# Transistor-theremin_2026-03-18_10-14-34.net
KiCad netlist of a schematic drawn in EasyEDA Pro
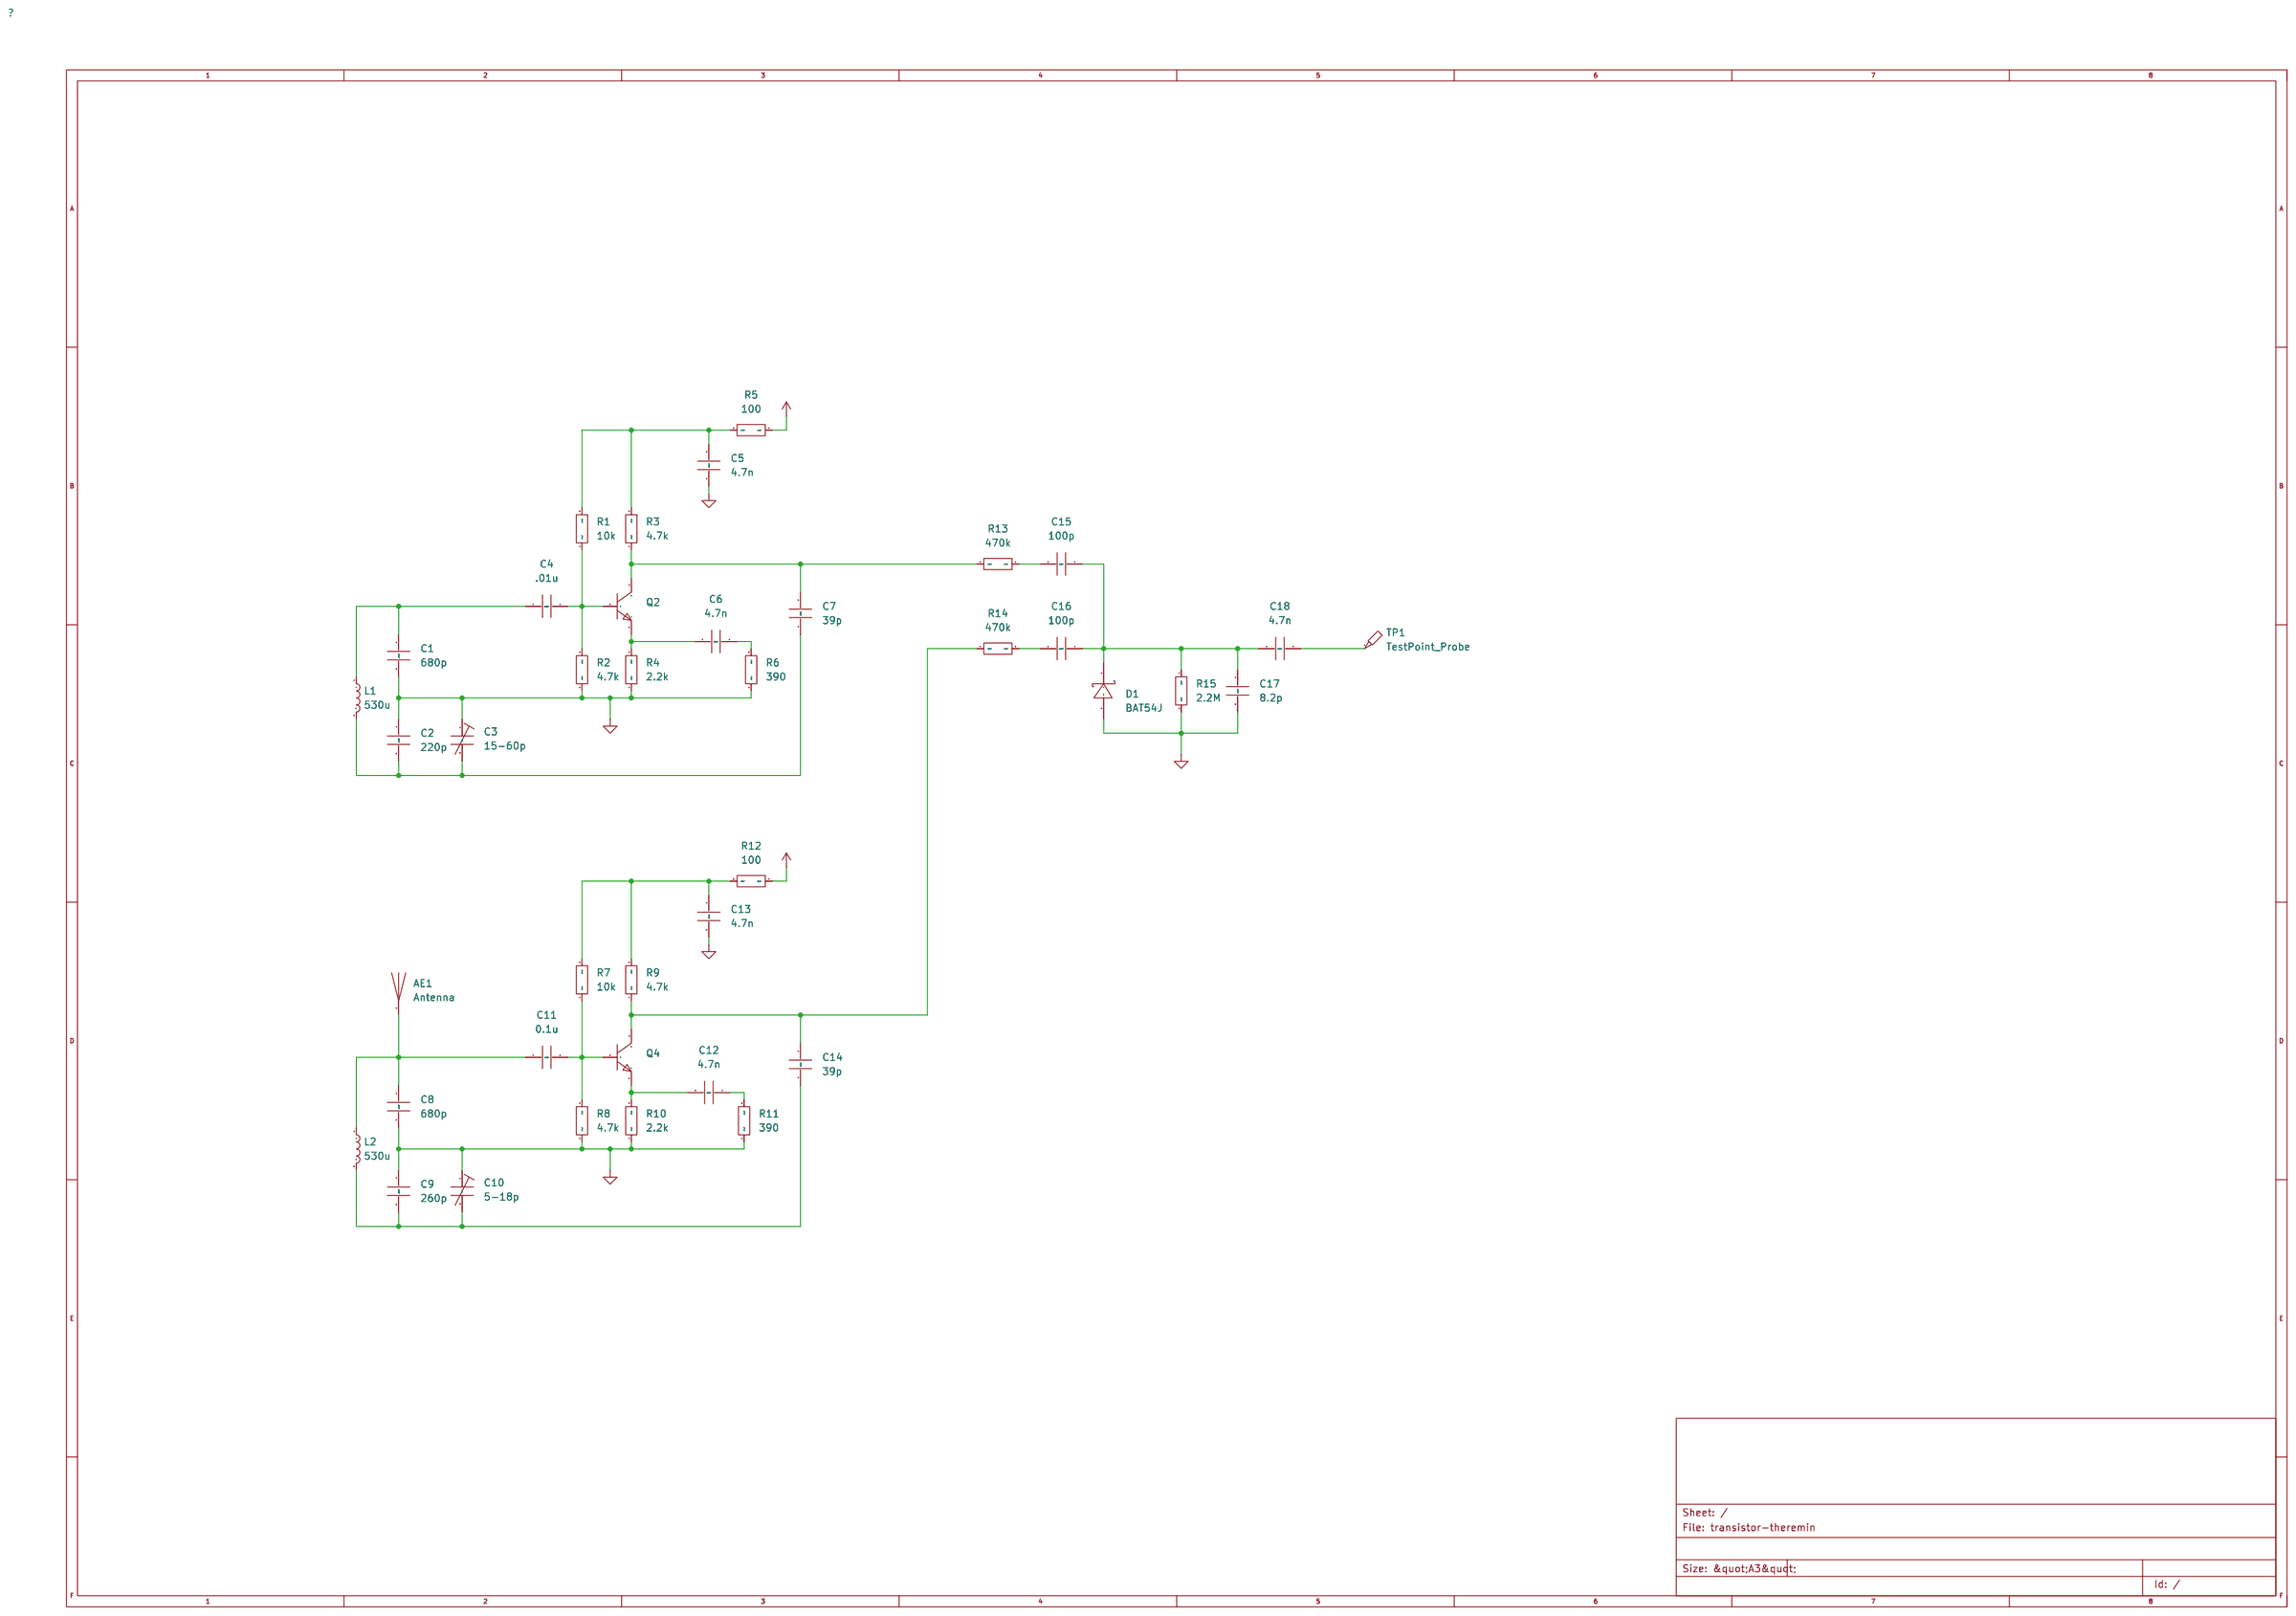
[diagram p0: schematic sheet]

(export (version "E")
  (design (tool "Eeschema 10.0.6"))
  (components
    (comp (ref "AE1") (value "Antenna") (libsource (lib "easyedapro") (part "Device_Antenna")))
    (comp (ref "C1")
      (value "680p")
      (description "Unpolarized capacitor")
      (libsource (lib "easyedapro") (part "Device_C"))
    )
    (comp (ref "C2")
      (value "220p")
      (description "Unpolarized capacitor")
      (libsource (lib "easyedapro") (part "Device_C"))
    )
    (comp (ref "C3")
      (value "15-60p")
      (description "Trimmable capacitor")
      (libsource (lib "easyedapro") (part "Device_C_Trim"))
    )
    (comp (ref "C4")
      (value ".01u")
      (description "Unpolarized capacitor")
      (libsource (lib "easyedapro") (part "Device_C"))
    )
    (comp (ref "C5")
      (value "4.7n")
      (description "Unpolarized capacitor")
      (libsource (lib "easyedapro") (part "Device_C"))
    )
    (comp (ref "C6")
      (value "4.7n")
      (description "Unpolarized capacitor")
      (libsource (lib "easyedapro") (part "Device_C"))
    )
    (comp (ref "C7")
      (value "39p")
      (description "Unpolarized capacitor")
      (libsource (lib "easyedapro") (part "Device_C"))
    )
    (comp (ref "C8")
      (value "680p")
      (description "Unpolarized capacitor")
      (libsource (lib "easyedapro") (part "Device_C"))
    )
    (comp (ref "C9")
      (value "260p")
      (description "Unpolarized capacitor")
      (libsource (lib "easyedapro") (part "Device_C"))
    )
    (comp (ref "C10")
      (value "5-18p")
      (description "Trimmable capacitor")
      (libsource (lib "easyedapro") (part "Device_C_Trim"))
    )
    (comp (ref "C11")
      (value "0.1u")
      (description "Unpolarized capacitor")
      (libsource (lib "easyedapro") (part "Device_C"))
    )
    (comp (ref "C12")
      (value "4.7n")
      (description "Unpolarized capacitor")
      (libsource (lib "easyedapro") (part "Device_C"))
    )
    (comp (ref "C13")
      (value "4.7n")
      (description "Unpolarized capacitor")
      (libsource (lib "easyedapro") (part "Device_C"))
    )
    (comp (ref "C14")
      (value "39p")
      (description "Unpolarized capacitor")
      (libsource (lib "easyedapro") (part "Device_C"))
    )
    (comp (ref "C15")
      (value "100p")
      (description "Unpolarized capacitor")
      (libsource (lib "easyedapro") (part "Device_C"))
    )
    (comp (ref "C16")
      (value "100p")
      (description "Unpolarized capacitor")
      (libsource (lib "easyedapro") (part "Device_C"))
    )
    (comp (ref "C17")
      (value "8.2p")
      (description "Unpolarized capacitor")
      (libsource (lib "easyedapro") (part "Device_C"))
    )
    (comp (ref "C18")
      (value "4.7n")
      (description "Unpolarized capacitor")
      (libsource (lib "easyedapro") (part "Device_C"))
    )
    (comp (ref "D1")
      (value "BAT54J")
      (footprint "easyedapro:SOD-323_L1.8-W1.3-LS2.5-RD")
      (fields (field (name "Manufacturer") "BLUE ROCKET(蓝箭)"))
      (libsource (lib "easyedapro") (part "BAT54J"))
    )
    (comp (ref "L1") (value "530u") (description "Inductor") (libsource (lib "easyedapro") (part "Device_L")))
    (comp (ref "L2") (value "530u") (description "Inductor") (libsource (lib "easyedapro") (part "Device_L")))
    (comp (ref "Q2")
      (value "~")
      (footprint "easyedapro:SOT-23-3_L2.9-W1.3-P1.90-LS2.4-BR")
      (fields (field (name "Manufacturer Part") "MMBT3904") (field (name "Manufacturer") "CJ(江苏长电/长晶)"))
      (libsource (lib "easyedapro") (part "MMBT3904"))
    )
    (comp (ref "Q4")
      (value "~")
      (footprint "easyedapro:SOT-23-3_L2.9-W1.3-P1.90-LS2.4-BR")
      (fields (field (name "Manufacturer Part") "MMBT3904") (field (name "Manufacturer") "CJ(江苏长电/长晶)"))
      (libsource (lib "easyedapro") (part "MMBT3904"))
    )
    (comp (ref "R1") (value "10k") (description "Resistor") (libsource (lib "easyedapro") (part "Device_R")))
    (comp (ref "R2") (value "4.7k") (description "Resistor") (libsource (lib "easyedapro") (part "Device_R")))
    (comp (ref "R3") (value "4.7k") (description "Resistor") (libsource (lib "easyedapro") (part "Device_R")))
    (comp (ref "R4") (value "2.2k") (description "Resistor") (libsource (lib "easyedapro") (part "Device_R")))
    (comp (ref "R5") (value "100") (description "Resistor") (libsource (lib "easyedapro") (part "Device_R")))
    (comp (ref "R6") (value "390") (description "Resistor") (libsource (lib "easyedapro") (part "Device_R")))
    (comp (ref "R7") (value "10k") (description "Resistor") (libsource (lib "easyedapro") (part "Device_R")))
    (comp (ref "R8") (value "4.7k") (description "Resistor") (libsource (lib "easyedapro") (part "Device_R")))
    (comp (ref "R9") (value "4.7k") (description "Resistor") (libsource (lib "easyedapro") (part "Device_R")))
    (comp (ref "R10")
      (value "2.2k")
      (description "Resistor")
      (libsource (lib "easyedapro") (part "Device_R"))
    )
    (comp (ref "R11") (value "390") (description "Resistor") (libsource (lib "easyedapro") (part "Device_R")))
    (comp (ref "R12") (value "100") (description "Resistor") (libsource (lib "easyedapro") (part "Device_R")))
    (comp (ref "R13")
      (value "470k")
      (description "Resistor")
      (libsource (lib "easyedapro") (part "Device_R"))
    )
    (comp (ref "R14")
      (value "470k")
      (description "Resistor")
      (libsource (lib "easyedapro") (part "Device_R"))
    )
    (comp (ref "R15")
      (value "2.2M")
      (description "Resistor")
      (libsource (lib "easyedapro") (part "Device_R"))
    )
    (comp (ref "TP1")
      (value "TestPoint_Probe")
      (description "test point (alternative probe-style design)")
      (libsource (lib "easyedapro") (part "Connector_TestPoint_Probe"))
    )
  )
  (nets
    (net (code "1") (name "Net-(AE1-A)") (class "Default")
      (node (ref "AE1") (pin "1") (pinfunction "A_1") (pintype "input"))
      (node (ref "C11") (pin "1") (pinfunction "~_1") (pintype "unspecified"))
      (node (ref "C8") (pin "1") (pinfunction "~_1") (pintype "unspecified"))
      (node (ref "L2") (pin "1") (pinfunction "1_1") (pintype "unspecified"))
    )
    (net (code "2") (name "Net-(C1-~-Pad1)") (class "Default")
      (node (ref "C1") (pin "1") (pinfunction "~_1") (pintype "unspecified"))
      (node (ref "C4") (pin "1") (pinfunction "~_1") (pintype "unspecified"))
      (node (ref "L1") (pin "1") (pinfunction "1_1") (pintype "unspecified"))
    )
    (net (code "3") (name "Net-(C2-~-Pad2)") (class "Default")
      (node (ref "C2") (pin "2") (pinfunction "~_2") (pintype "unspecified"))
      (node (ref "C3") (pin "2") (pinfunction "~_2") (pintype "unspecified"))
      (node (ref "C7") (pin "1") (pinfunction "~_1") (pintype "unspecified"))
      (node (ref "L1") (pin "2") (pinfunction "2_2") (pintype "unspecified"))
    )
    (net (code "4") (name "Net-(C5-~-Pad2)") (class "Default")
      (node (ref "C5") (pin "2") (pinfunction "~_2") (pintype "unspecified"))
      (node (ref "R1") (pin "2") (pinfunction "~_2") (pintype "unspecified"))
      (node (ref "R3") (pin "2") (pinfunction "~_2") (pintype "unspecified"))
      (node (ref "R5") (pin "2") (pinfunction "~_2") (pintype "unspecified"))
    )
    (net (code "5") (name "Net-(C6-~-Pad1)") (class "Default")
      (node (ref "C6") (pin "1") (pinfunction "~_1") (pintype "unspecified"))
      (node (ref "R6") (pin "2") (pinfunction "~_2") (pintype "unspecified"))
    )
    (net (code "6") (name "Net-(C10-~-Pad2)") (class "Default")
      (node (ref "C10") (pin "2") (pinfunction "~_2") (pintype "unspecified"))
      (node (ref "C14") (pin "1") (pinfunction "~_1") (pintype "unspecified"))
      (node (ref "C9") (pin "2") (pinfunction "~_2") (pintype "unspecified"))
      (node (ref "L2") (pin "2") (pinfunction "2_2") (pintype "unspecified"))
    )
    (net (code "7") (name "Net-(C12-~-Pad1)") (class "Default")
      (node (ref "C12") (pin "1") (pinfunction "~_1") (pintype "unspecified"))
      (node (ref "R11") (pin "2") (pinfunction "~_2") (pintype "unspecified"))
    )
    (net (code "8") (name "Net-(C13-~-Pad2)") (class "Default")
      (node (ref "C13") (pin "2") (pinfunction "~_2") (pintype "unspecified"))
      (node (ref "R12") (pin "2") (pinfunction "~_2") (pintype "unspecified"))
      (node (ref "R7") (pin "2") (pinfunction "~_2") (pintype "unspecified"))
      (node (ref "R9") (pin "2") (pinfunction "~_2") (pintype "unspecified"))
    )
    (net (code "9") (name "Net-(C15-~-Pad1)") (class "Default")
      (node (ref "C15") (pin "1") (pinfunction "~_1") (pintype "unspecified"))
      (node (ref "C16") (pin "1") (pinfunction "~_1") (pintype "unspecified"))
      (node (ref "C17") (pin "1") (pinfunction "~_1") (pintype "unspecified"))
      (node (ref "C18") (pin "1") (pinfunction "~_1") (pintype "unspecified"))
      (node (ref "D1") (pin "1") (pinfunction "1_1") (pintype "unspecified"))
      (node (ref "R15") (pin "1") (pinfunction "~_1") (pintype "unspecified"))
    )
    (net (code "10") (name "Net-(C15-~-Pad2)") (class "Default")
      (node (ref "C15") (pin "2") (pinfunction "~_2") (pintype "unspecified"))
      (node (ref "R13") (pin "1") (pinfunction "~_1") (pintype "unspecified"))
    )
    (net (code "11") (name "Net-(C16-~-Pad2)") (class "Default")
      (node (ref "C16") (pin "2") (pinfunction "~_2") (pintype "unspecified"))
      (node (ref "R14") (pin "1") (pinfunction "~_1") (pintype "unspecified"))
    )
    (net (code "12") (name "Net-(C18-~-Pad2)") (class "Default")
      (node (ref "C18") (pin "2") (pinfunction "~_2") (pintype "unspecified"))
      (node (ref "TP1") (pin "1") (pinfunction "1_1") (pintype "unspecified"))
    )
    (net (code "13") (name "Net-(Q2-B)") (class "Default")
      (node (ref "C4") (pin "2") (pinfunction "~_2") (pintype "unspecified"))
      (node (ref "Q2") (pin "1") (pinfunction "B_1") (pintype "input"))
      (node (ref "R1") (pin "1") (pinfunction "~_1") (pintype "unspecified"))
      (node (ref "R2") (pin "1") (pinfunction "~_1") (pintype "unspecified"))
    )
    (net (code "14") (name "Net-(Q2-C)") (class "Default")
      (node (ref "C7") (pin "2") (pinfunction "~_2") (pintype "unspecified"))
      (node (ref "Q2") (pin "3") (pinfunction "C_3") (pintype "input"))
      (node (ref "R13") (pin "2") (pinfunction "~_2") (pintype "unspecified"))
      (node (ref "R3") (pin "1") (pinfunction "~_1") (pintype "unspecified"))
    )
    (net (code "15") (name "Net-(Q2-E)") (class "Default")
      (node (ref "C6") (pin "2") (pinfunction "~_2") (pintype "unspecified"))
      (node (ref "Q2") (pin "2") (pinfunction "E_2") (pintype "input"))
      (node (ref "R4") (pin "2") (pinfunction "~_2") (pintype "unspecified"))
    )
    (net (code "16") (name "Net-(Q4-B)") (class "Default")
      (node (ref "C11") (pin "2") (pinfunction "~_2") (pintype "unspecified"))
      (node (ref "Q4") (pin "1") (pinfunction "B_1") (pintype "input"))
      (node (ref "R7") (pin "1") (pinfunction "~_1") (pintype "unspecified"))
      (node (ref "R8") (pin "1") (pinfunction "~_1") (pintype "unspecified"))
    )
    (net (code "17") (name "Net-(Q4-C)") (class "Default")
      (node (ref "C14") (pin "2") (pinfunction "~_2") (pintype "unspecified"))
      (node (ref "Q4") (pin "3") (pinfunction "C_3") (pintype "input"))
      (node (ref "R14") (pin "2") (pinfunction "~_2") (pintype "unspecified"))
      (node (ref "R9") (pin "1") (pinfunction "~_1") (pintype "unspecified"))
    )
    (net (code "18") (name "Net-(Q4-E)") (class "Default")
      (node (ref "C12") (pin "2") (pinfunction "~_2") (pintype "unspecified"))
      (node (ref "Q4") (pin "2") (pinfunction "E_2") (pintype "input"))
      (node (ref "R10") (pin "2") (pinfunction "~_2") (pintype "unspecified"))
    )
    (net (code "19") (name "POWER_+12V") (class "Default")
      (node (ref "R12") (pin "1") (pinfunction "~_1") (pintype "unspecified"))
      (node (ref "R5") (pin "1") (pinfunction "~_1") (pintype "unspecified"))
    )
    (net (code "20") (name "POWER_GND") (class "Default")
      (node (ref "C1") (pin "2") (pinfunction "~_2") (pintype "unspecified"))
      (node (ref "C10") (pin "1") (pinfunction "~_1") (pintype "unspecified"))
      (node (ref "C13") (pin "1") (pinfunction "~_1") (pintype "unspecified"))
      (node (ref "C17") (pin "2") (pinfunction "~_2") (pintype "unspecified"))
      (node (ref "C2") (pin "1") (pinfunction "~_1") (pintype "unspecified"))
      (node (ref "C3") (pin "1") (pinfunction "~_1") (pintype "unspecified"))
      (node (ref "C5") (pin "1") (pinfunction "~_1") (pintype "unspecified"))
      (node (ref "C8") (pin "2") (pinfunction "~_2") (pintype "unspecified"))
      (node (ref "C9") (pin "1") (pinfunction "~_1") (pintype "unspecified"))
      (node (ref "D1") (pin "2") (pinfunction "2_2") (pintype "unspecified"))
      (node (ref "R10") (pin "1") (pinfunction "~_1") (pintype "unspecified"))
      (node (ref "R11") (pin "1") (pinfunction "~_1") (pintype "unspecified"))
      (node (ref "R15") (pin "2") (pinfunction "~_2") (pintype "unspecified"))
      (node (ref "R2") (pin "2") (pinfunction "~_2") (pintype "unspecified"))
      (node (ref "R4") (pin "1") (pinfunction "~_1") (pintype "unspecified"))
      (node (ref "R6") (pin "1") (pinfunction "~_1") (pintype "unspecified"))
      (node (ref "R8") (pin "2") (pinfunction "~_2") (pintype "unspecified"))
    )
  )
)
